# PCB_Timbangan.net
KiCad netlist of a schematic drawn in EasyEDA
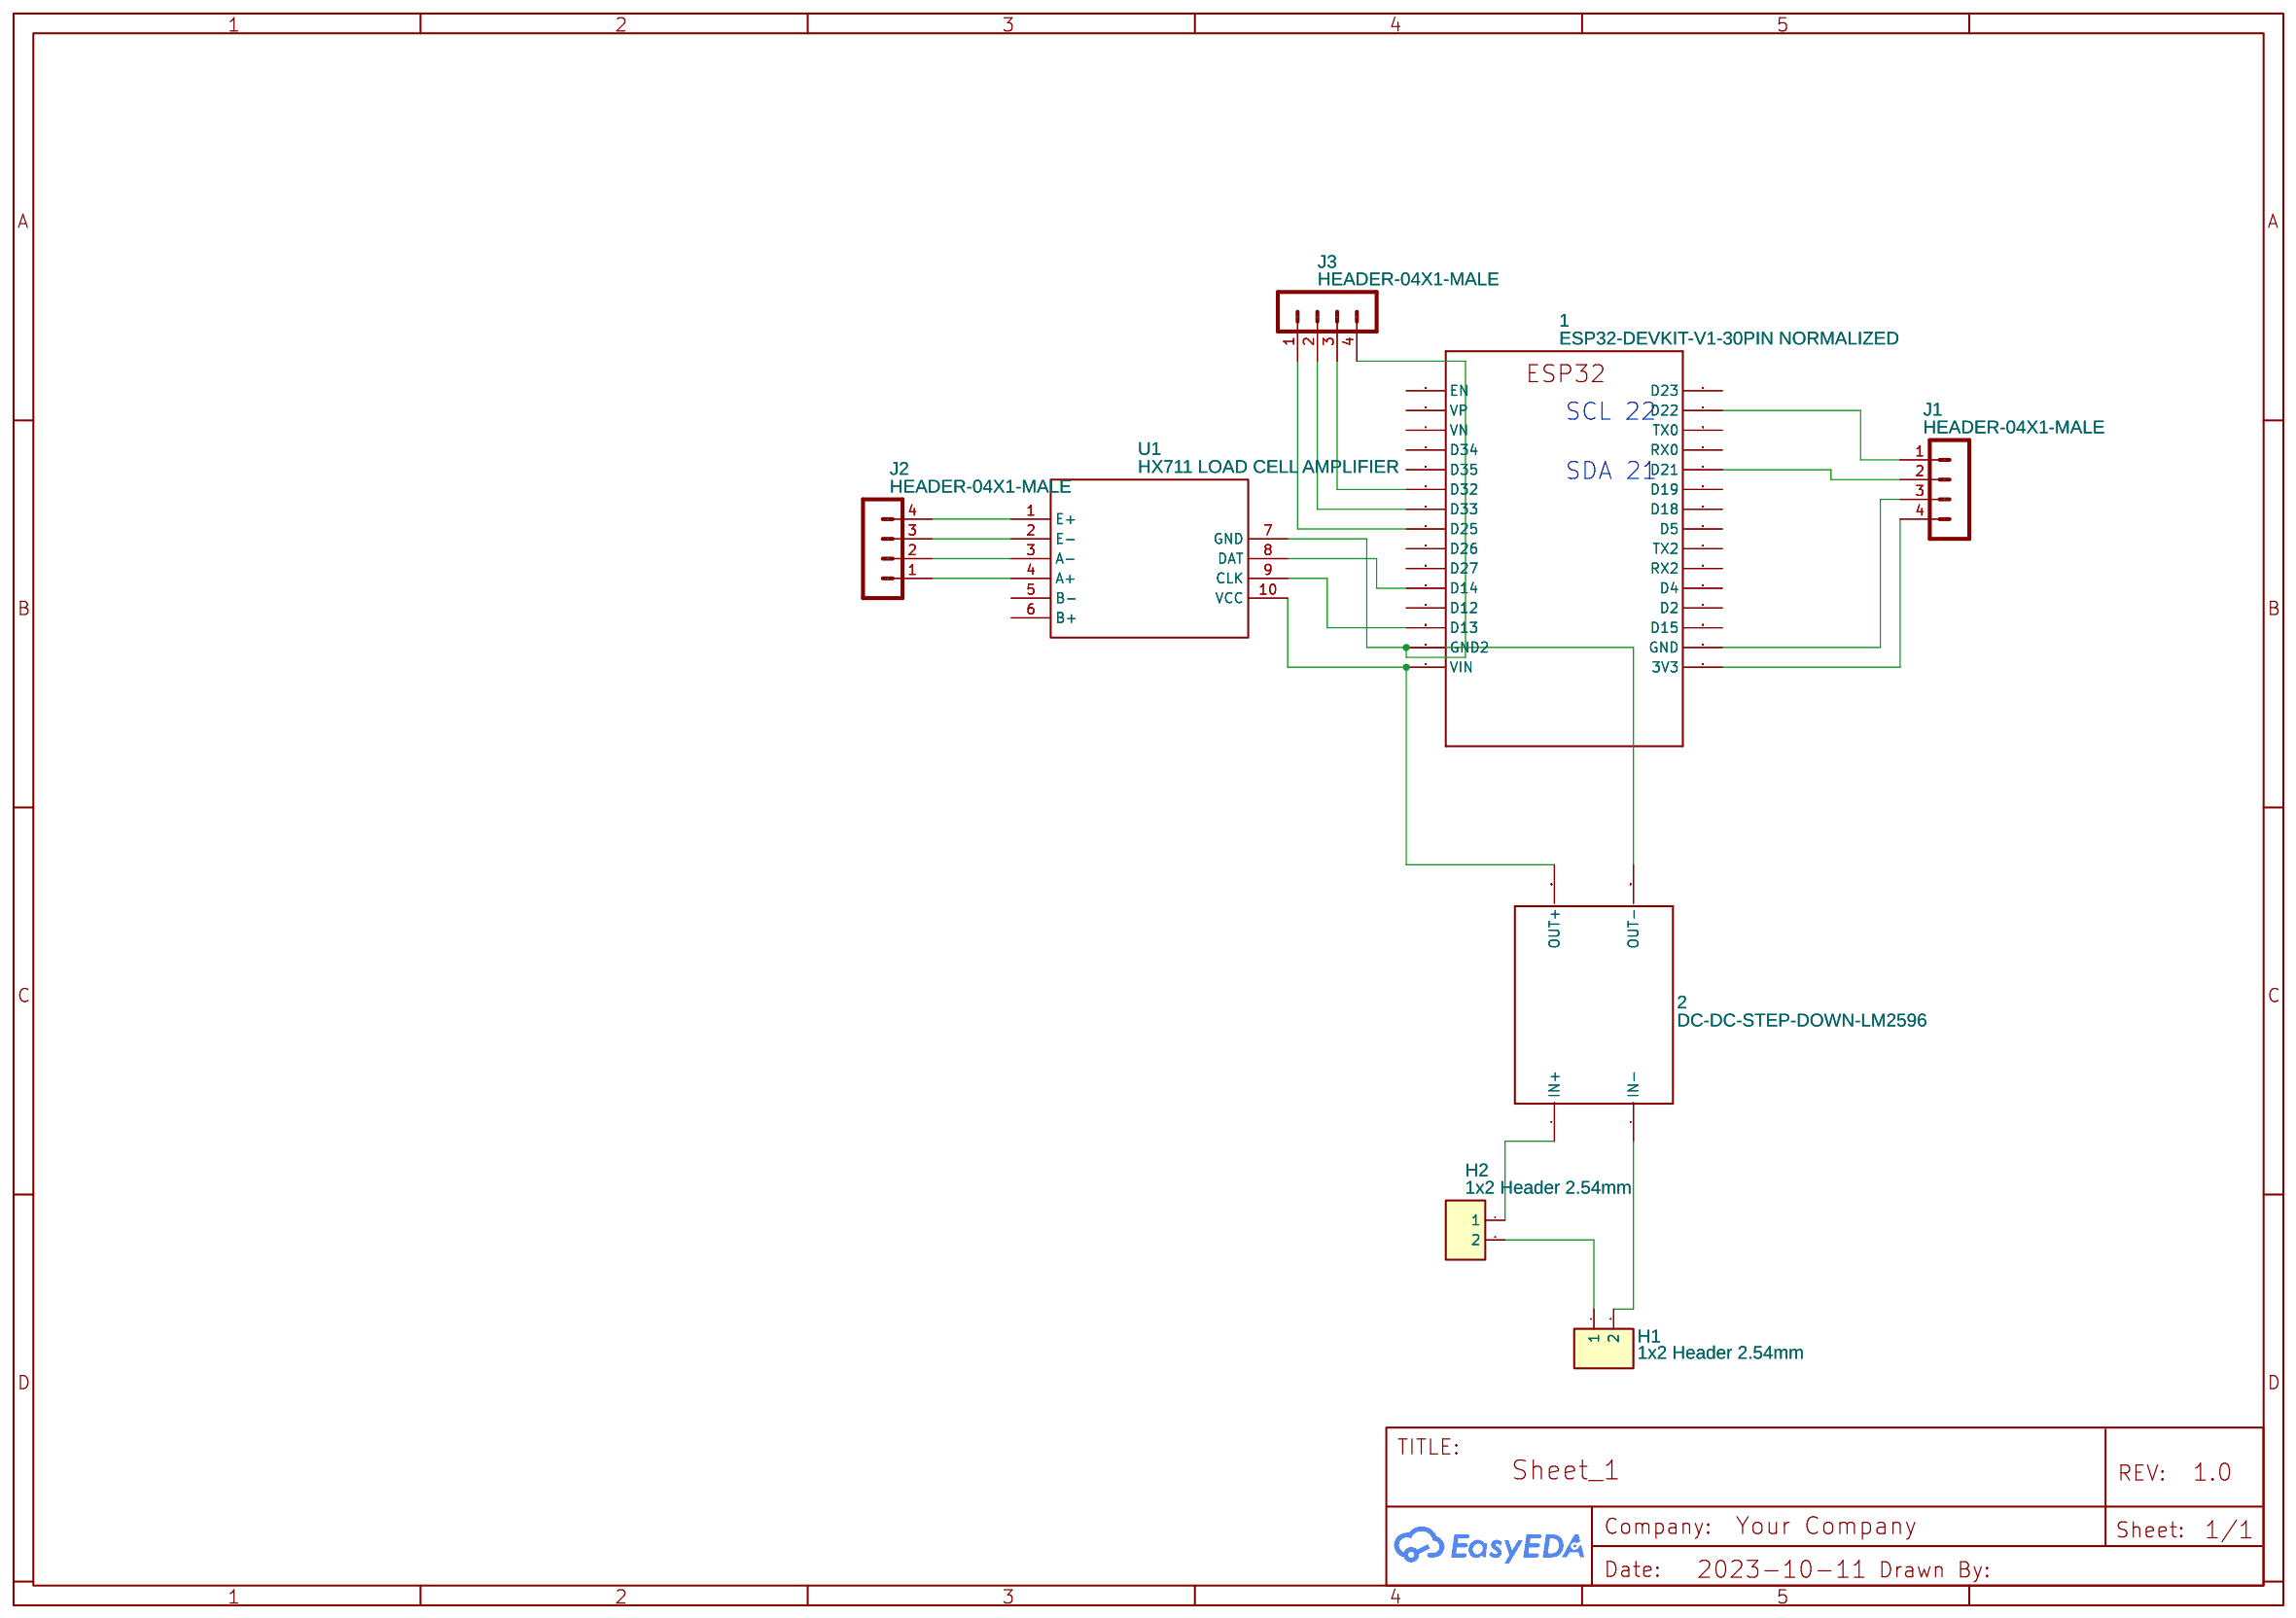
[diagram p0: schematic sheet]

(export (version "E")
  (design (tool "Eeschema 10.0.6"))
  (components
    (comp (ref "1")
      (value "ESP32-DEVKIT-V1-30PIN NORMALIZED")
      (libsource (lib "") (part "ESP32-DEVKIT-V1-30PIN"))
    )
    (comp (ref "2") (value "DC-DC-STEP-DOWN-LM2596") (libsource (lib "") (part "DC-DC-STEP-DOWN-LM2596")))
    (comp (ref "H1")
      (value "1x2 Header 2.54mm")
      (fields (field (name "Manufacturer Part") "New SchematicLib"))
      (libsource (lib "") (part "1x2 Header 2.54mm"))
    )
    (comp (ref "H2")
      (value "1x2 Header 2.54mm")
      (fields (field (name "Manufacturer Part") "New SchematicLib"))
      (libsource (lib "") (part "1x2 Header 2.54mm_1"))
    )
    (comp (ref "J1") (value "HEADER-04X1-MALE") (libsource (lib "") (part "HEADER-04X1-MALE_2")))
    (comp (ref "J2") (value "HEADER-04X1-MALE") (libsource (lib "") (part "HEADER-04X1-MALE_1")))
    (comp (ref "J3") (value "HEADER-04X1-MALE") (libsource (lib "") (part "HEADER-04X1-MALE")))
    (comp (ref "U1")
      (value "HX711 LOAD CELL AMPLIFIER")
      (libsource (lib "") (part "HX711 LOAD CELL AMPLIFIER"))
    )
  )
  (nets
    (net (code "1") (name "Net-(1-Pad3V3)") (class "Default")
      (node (ref "1") (pin "3V3") (pinfunction "3V3_3V3") (pintype "unspecified"))
      (node (ref "J1") (pin "4") (pinfunction "4_4") (pintype "unspecified"))
    )
    (net (code "2") (name "Net-(1-PadD21)") (class "Default")
      (node (ref "1") (pin "D21") (pinfunction "D21_D21") (pintype "unspecified"))
      (node (ref "J1") (pin "2") (pinfunction "2_2") (pintype "unspecified"))
    )
    (net (code "3") (name "Net-(1-PadD22)") (class "Default")
      (node (ref "1") (pin "D22") (pinfunction "D22_D22") (pintype "unspecified"))
      (node (ref "J1") (pin "1") (pinfunction "1_1") (pintype "unspecified"))
    )
    (net (code "4") (name "Net-(1-PadD25)") (class "Default")
      (node (ref "1") (pin "D25") (pinfunction "D25_D25") (pintype "unspecified"))
      (node (ref "J3") (pin "1") (pinfunction "1_1") (pintype "unspecified"))
    )
    (net (code "5") (name "Net-(1-PadD32)") (class "Default")
      (node (ref "1") (pin "D32") (pinfunction "D32_D32") (pintype "unspecified"))
      (node (ref "J3") (pin "3") (pinfunction "3_3") (pintype "unspecified"))
    )
    (net (code "6") (name "Net-(1-PadD33)") (class "Default")
      (node (ref "1") (pin "D33") (pinfunction "D33_D33") (pintype "unspecified"))
      (node (ref "J3") (pin "2") (pinfunction "2_2") (pintype "unspecified"))
    )
    (net (code "7") (name "Net-(1-PadGND)") (class "Default")
      (node (ref "1") (pin "GND") (pinfunction "GND_GND") (pintype "unspecified"))
      (node (ref "J1") (pin "3") (pinfunction "3_3") (pintype "unspecified"))
    )
    (net (code "8") (name "Net-(2-PadIN+)") (class "Default")
      (node (ref "2") (pin "IN+") (pinfunction "IN+_IN+") (pintype "bidirectional"))
      (node (ref "H2") (pin "1") (pinfunction "1_1") (pintype "unspecified"))
    )
    (net (code "9") (name "Net-(2-PadIN-)") (class "Default")
      (node (ref "2") (pin "IN-") (pinfunction "IN-_IN-") (pintype "bidirectional"))
      (node (ref "H1") (pin "2") (pinfunction "2_2") (pintype "unspecified"))
    )
    (net (code "10") (name "Net-(H1-Pad1)") (class "Default")
      (node (ref "H1") (pin "1") (pinfunction "1_1") (pintype "unspecified"))
      (node (ref "H2") (pin "2") (pinfunction "2_2") (pintype "unspecified"))
    )
    (net (code "11") (name "Net-(U1-A+)") (class "Default")
      (node (ref "J2") (pin "1") (pinfunction "1_1") (pintype "unspecified"))
      (node (ref "U1") (pin "4") (pinfunction "A+_4") (pintype "unspecified"))
    )
    (net (code "12") (name "Net-(U1-A-)") (class "Default")
      (node (ref "J2") (pin "2") (pinfunction "2_2") (pintype "unspecified"))
      (node (ref "U1") (pin "3") (pinfunction "A-_3") (pintype "unspecified"))
    )
    (net (code "13") (name "Net-(U1-CLK)") (class "Default")
      (node (ref "1") (pin "D13") (pinfunction "D13_D13") (pintype "unspecified"))
      (node (ref "U1") (pin "9") (pinfunction "CLK_9") (pintype "unspecified"))
    )
    (net (code "14") (name "Net-(U1-DAT)") (class "Default")
      (node (ref "1") (pin "D14") (pinfunction "D14_D14") (pintype "unspecified"))
      (node (ref "U1") (pin "8") (pinfunction "DAT_8") (pintype "unspecified"))
    )
    (net (code "15") (name "Net-(U1-E+)") (class "Default")
      (node (ref "J2") (pin "4") (pinfunction "4_4") (pintype "unspecified"))
      (node (ref "U1") (pin "1") (pinfunction "E+_1") (pintype "unspecified"))
    )
    (net (code "16") (name "Net-(U1-E-)") (class "Default")
      (node (ref "J2") (pin "3") (pinfunction "3_3") (pintype "unspecified"))
      (node (ref "U1") (pin "2") (pinfunction "E-_2") (pintype "unspecified"))
    )
    (net (code "17") (name "Net-(U1-GND)") (class "Default")
      (node (ref "1") (pin "GND2") (pinfunction "GND2_GND2") (pintype "unspecified"))
      (node (ref "2") (pin "OUT-") (pinfunction "OUT-_OUT-") (pintype "bidirectional"))
      (node (ref "J3") (pin "4") (pinfunction "4_4") (pintype "unspecified"))
      (node (ref "U1") (pin "7") (pinfunction "GND_7") (pintype "unspecified"))
    )
    (net (code "18") (name "Net-(U1-VCC)") (class "Default")
      (node (ref "1") (pin "VIN") (pinfunction "VIN_VIN") (pintype "unspecified"))
      (node (ref "2") (pin "OUT+") (pinfunction "OUT+_OUT+") (pintype "bidirectional"))
      (node (ref "U1") (pin "10") (pinfunction "VCC_10") (pintype "unspecified"))
    )
    (net (code "19") (name "unconnected-(1-PadD2)") (class "Default")
      (node (ref "1") (pin "D2") (pinfunction "D2_D2") (pintype "unspecified"))
    )
    (net (code "20") (name "unconnected-(1-PadD4)") (class "Default")
      (node (ref "1") (pin "D4") (pinfunction "D4_D4") (pintype "unspecified"))
    )
    (net (code "21") (name "unconnected-(1-PadD5)") (class "Default")
      (node (ref "1") (pin "D5") (pinfunction "D5_D5") (pintype "unspecified"))
    )
    (net (code "22") (name "unconnected-(1-PadD12)") (class "Default")
      (node (ref "1") (pin "D12") (pinfunction "D12_D12") (pintype "unspecified"))
    )
    (net (code "23") (name "unconnected-(1-PadD15)") (class "Default")
      (node (ref "1") (pin "D15") (pinfunction "D15_D15") (pintype "unspecified"))
    )
    (net (code "24") (name "unconnected-(1-PadD18)") (class "Default")
      (node (ref "1") (pin "D18") (pinfunction "D18_D18") (pintype "unspecified"))
    )
    (net (code "25") (name "unconnected-(1-PadD19)") (class "Default")
      (node (ref "1") (pin "D19") (pinfunction "D19_D19") (pintype "unspecified"))
    )
    (net (code "26") (name "unconnected-(1-PadD23)") (class "Default")
      (node (ref "1") (pin "D23") (pinfunction "D23_D23") (pintype "unspecified"))
    )
    (net (code "27") (name "unconnected-(1-PadD26)") (class "Default")
      (node (ref "1") (pin "D26") (pinfunction "D26_D26") (pintype "unspecified"))
    )
    (net (code "28") (name "unconnected-(1-PadD27)") (class "Default")
      (node (ref "1") (pin "D27") (pinfunction "D27_D27") (pintype "unspecified"))
    )
    (net (code "29") (name "unconnected-(1-PadD34)") (class "Default")
      (node (ref "1") (pin "D34") (pinfunction "D34_D34") (pintype "unspecified"))
    )
    (net (code "30") (name "unconnected-(1-PadD35)") (class "Default")
      (node (ref "1") (pin "D35") (pinfunction "D35_D35") (pintype "unspecified"))
    )
    (net (code "31") (name "unconnected-(1-PadEN)") (class "Default")
      (node (ref "1") (pin "EN") (pinfunction "EN_EN") (pintype "unspecified"))
    )
    (net (code "32") (name "unconnected-(1-PadRX0)") (class "Default")
      (node (ref "1") (pin "RX0") (pinfunction "RX0_RX0") (pintype "unspecified"))
    )
    (net (code "33") (name "unconnected-(1-PadRX2)") (class "Default")
      (node (ref "1") (pin "RX2") (pinfunction "RX2_RX2") (pintype "unspecified"))
    )
    (net (code "34") (name "unconnected-(1-PadTX0)") (class "Default")
      (node (ref "1") (pin "TX0") (pinfunction "TX0_TX0") (pintype "unspecified"))
    )
    (net (code "35") (name "unconnected-(1-PadTX2)") (class "Default")
      (node (ref "1") (pin "TX2") (pinfunction "TX2_TX2") (pintype "unspecified"))
    )
    (net (code "36") (name "unconnected-(1-PadVN)") (class "Default")
      (node (ref "1") (pin "VN") (pinfunction "VN_VN") (pintype "unspecified"))
    )
    (net (code "37") (name "unconnected-(1-PadVP)") (class "Default")
      (node (ref "1") (pin "VP") (pinfunction "VP_VP") (pintype "unspecified"))
    )
    (net (code "38") (name "unconnected-(U1-B+-Pad6)") (class "Default")
      (node (ref "U1") (pin "6") (pinfunction "B+_6") (pintype "unspecified"))
    )
    (net (code "39") (name "unconnected-(U1-B--Pad5)") (class "Default")
      (node (ref "U1") (pin "5") (pinfunction "B-_5") (pintype "unspecified"))
    )
  )
)
